# M-Controller_REV-A.net
KiCad netlist of a schematic drawn in EAGLE
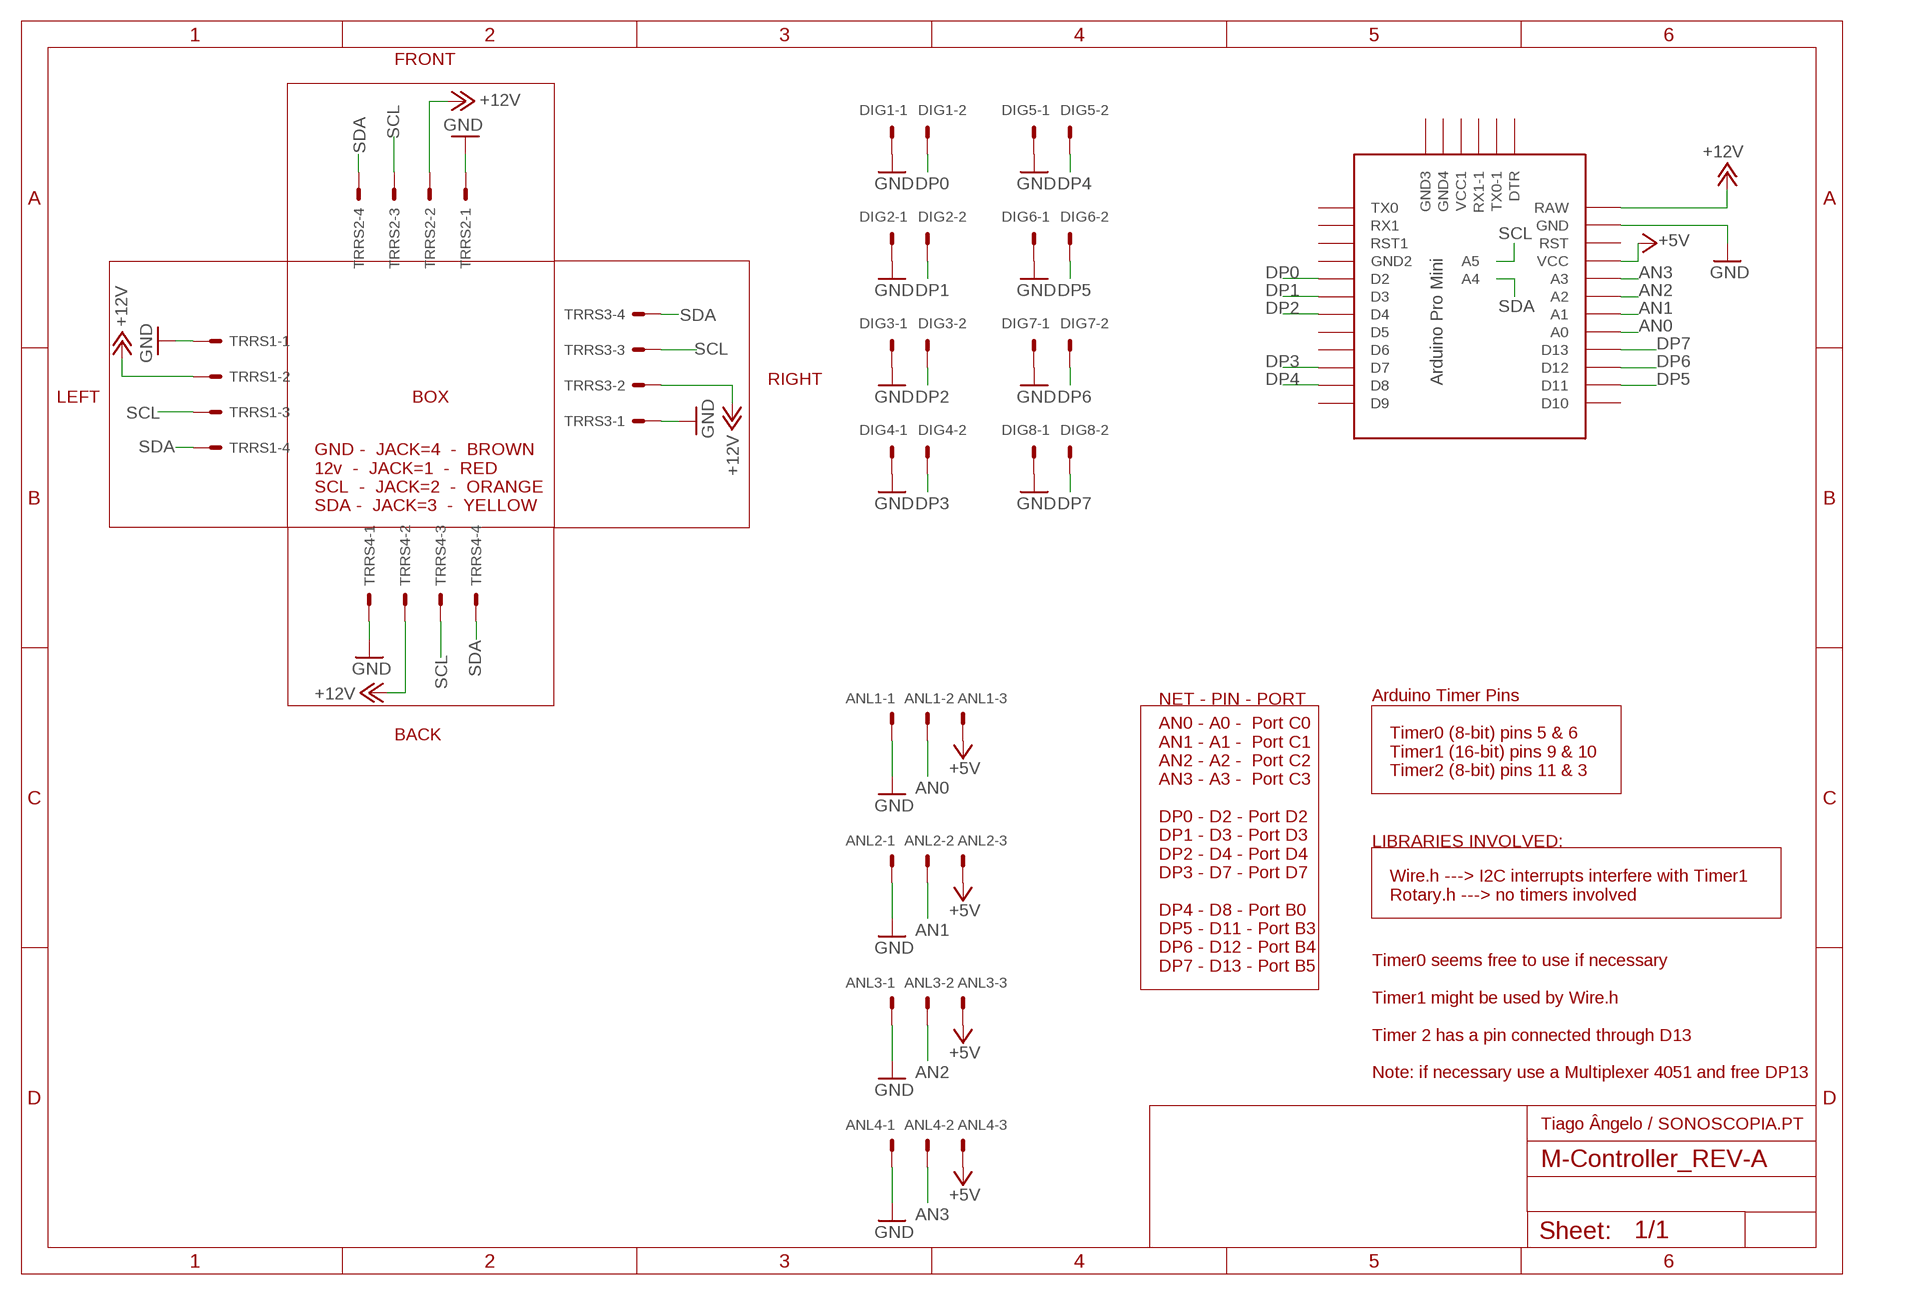
[diagram p0: schematic, sheet 1]

(export (version "E")
  (design (tool "Eeschema 10.0.6"))
  (components
    (comp (ref "ANL1")
      (value "22-27-2031-03")
      (footprint "eagle-import:6410-03")
      (libsource (lib "eagle-import") (part "22-?-0327-2031"))
    )
    (comp (ref "ANL2")
      (value "22-27-2031-03")
      (footprint "eagle-import:6410-03")
      (libsource (lib "eagle-import") (part "22-?-0327-2031"))
    )
    (comp (ref "ANL3")
      (value "22-27-2031-03")
      (footprint "eagle-import:6410-03")
      (libsource (lib "eagle-import") (part "22-?-0327-2031"))
    )
    (comp (ref "ANL4")
      (value "22-27-2031-03")
      (footprint "eagle-import:6410-03")
      (libsource (lib "eagle-import") (part "22-?-0327-2031"))
    )
    (comp (ref "DIG1")
      (value "22-27-2021-02")
      (footprint "eagle-import:6410-02")
      (libsource (lib "eagle-import") (part "22-?-0227-2021"))
    )
    (comp (ref "DIG2")
      (value "22-27-2021-02")
      (footprint "eagle-import:6410-02")
      (libsource (lib "eagle-import") (part "22-?-0227-2021"))
    )
    (comp (ref "DIG3")
      (value "22-27-2021-02")
      (footprint "eagle-import:6410-02")
      (libsource (lib "eagle-import") (part "22-?-0227-2021"))
    )
    (comp (ref "DIG4")
      (value "22-27-2021-02")
      (footprint "eagle-import:6410-02")
      (libsource (lib "eagle-import") (part "22-?-0227-2021"))
    )
    (comp (ref "DIG5")
      (value "22-27-2021-02")
      (footprint "eagle-import:6410-02")
      (libsource (lib "eagle-import") (part "22-?-0227-2021"))
    )
    (comp (ref "DIG6")
      (value "22-27-2021-02")
      (footprint "eagle-import:6410-02")
      (libsource (lib "eagle-import") (part "22-?-0227-2021"))
    )
    (comp (ref "DIG7")
      (value "22-27-2021-02")
      (footprint "eagle-import:6410-02")
      (libsource (lib "eagle-import") (part "22-?-0227-2021"))
    )
    (comp (ref "DIG8")
      (value "22-27-2021-02")
      (footprint "eagle-import:6410-02")
      (libsource (lib "eagle-import") (part "22-?-0227-2021"))
    )
    (comp (ref "TRRS1")
      (value "22-27-2041-04")
      (footprint "eagle-import:6410-04")
      (libsource (lib "eagle-import") (part "22-?-0427-2041"))
    )
    (comp (ref "TRRS2")
      (value "22-27-2041-04")
      (footprint "eagle-import:6410-04")
      (libsource (lib "eagle-import") (part "22-?-0427-2041"))
    )
    (comp (ref "TRRS3")
      (value "22-27-2041-04")
      (footprint "eagle-import:6410-04")
      (libsource (lib "eagle-import") (part "22-?-0427-2041"))
    )
    (comp (ref "TRRS4")
      (value "22-27-2041-04")
      (footprint "eagle-import:6410-04")
      (libsource (lib "eagle-import") (part "22-?-0427-2041"))
    )
    (comp (ref "U$1")
      (value "PRO-MINI-2")
      (footprint "eagle-import:PRO-MINI-2")
      (libsource (lib "eagle-import") (part "PRO-MINI-2"))
    )
  )
  (nets
    (net (code "1") (name "+5V") (class "Default")
      (node (ref "ANL1") (pin "3") (pinfunction "S_3") (pintype "passive"))
      (node (ref "ANL2") (pin "3") (pinfunction "S_3") (pintype "passive"))
      (node (ref "ANL3") (pin "3") (pinfunction "S_3") (pintype "passive"))
      (node (ref "ANL4") (pin "3") (pinfunction "S_3") (pintype "passive"))
      (node (ref "U$1") (pin "VCC") (pinfunction "VCC_VCC") (pintype "bidirectional"))
    )
    (net (code "2") (name "+12V") (class "Default")
      (node (ref "TRRS1") (pin "2") (pinfunction "S_2") (pintype "passive"))
      (node (ref "TRRS2") (pin "2") (pinfunction "S_2") (pintype "passive"))
      (node (ref "TRRS3") (pin "2") (pinfunction "S_2") (pintype "passive"))
      (node (ref "TRRS4") (pin "2") (pinfunction "S_2") (pintype "passive"))
      (node (ref "U$1") (pin "RAW") (pinfunction "RAW_RAW") (pintype "bidirectional"))
    )
    (net (code "3") (name "/AN0") (class "Default")
      (node (ref "ANL1") (pin "2") (pinfunction "S_2") (pintype "passive"))
      (node (ref "U$1") (pin "A0") (pinfunction "A0_A0") (pintype "bidirectional"))
    )
    (net (code "4") (name "/AN1") (class "Default")
      (node (ref "ANL2") (pin "2") (pinfunction "S_2") (pintype "passive"))
      (node (ref "U$1") (pin "A1") (pinfunction "A1_A1") (pintype "bidirectional"))
    )
    (net (code "5") (name "/AN2") (class "Default")
      (node (ref "ANL3") (pin "2") (pinfunction "S_2") (pintype "passive"))
      (node (ref "U$1") (pin "A2") (pinfunction "A2_A2") (pintype "bidirectional"))
    )
    (net (code "6") (name "/AN3") (class "Default")
      (node (ref "ANL4") (pin "2") (pinfunction "S_2") (pintype "passive"))
      (node (ref "U$1") (pin "A3") (pinfunction "A3_A3") (pintype "bidirectional"))
    )
    (net (code "7") (name "/DP0") (class "Default")
      (node (ref "DIG1") (pin "2") (pinfunction "S_2") (pintype "passive"))
      (node (ref "U$1") (pin "D2") (pinfunction "D2_D2") (pintype "bidirectional"))
    )
    (net (code "8") (name "/DP1") (class "Default")
      (node (ref "DIG2") (pin "2") (pinfunction "S_2") (pintype "passive"))
      (node (ref "U$1") (pin "D3") (pinfunction "D3_D3") (pintype "bidirectional"))
    )
    (net (code "9") (name "/DP2") (class "Default")
      (node (ref "DIG3") (pin "2") (pinfunction "S_2") (pintype "passive"))
      (node (ref "U$1") (pin "D4") (pinfunction "D4_D4") (pintype "bidirectional"))
    )
    (net (code "10") (name "/DP3") (class "Default")
      (node (ref "DIG4") (pin "2") (pinfunction "S_2") (pintype "passive"))
      (node (ref "U$1") (pin "D7") (pinfunction "D7_D7") (pintype "bidirectional"))
    )
    (net (code "11") (name "/DP4") (class "Default")
      (node (ref "DIG5") (pin "2") (pinfunction "S_2") (pintype "passive"))
      (node (ref "U$1") (pin "D8") (pinfunction "D8_D8") (pintype "bidirectional"))
    )
    (net (code "12") (name "/DP5") (class "Default")
      (node (ref "DIG6") (pin "2") (pinfunction "S_2") (pintype "passive"))
      (node (ref "U$1") (pin "D11") (pinfunction "D11_D11") (pintype "bidirectional"))
    )
    (net (code "13") (name "/DP6") (class "Default")
      (node (ref "DIG7") (pin "2") (pinfunction "S_2") (pintype "passive"))
      (node (ref "U$1") (pin "D12") (pinfunction "D12_D12") (pintype "bidirectional"))
    )
    (net (code "14") (name "/DP7") (class "Default")
      (node (ref "DIG8") (pin "2") (pinfunction "S_2") (pintype "passive"))
      (node (ref "U$1") (pin "D13") (pinfunction "D13_D13") (pintype "bidirectional"))
    )
    (net (code "15") (name "/SCL") (class "Default")
      (node (ref "TRRS1") (pin "3") (pinfunction "S_3") (pintype "passive"))
      (node (ref "TRRS2") (pin "3") (pinfunction "S_3") (pintype "passive"))
      (node (ref "TRRS3") (pin "3") (pinfunction "S_3") (pintype "passive"))
      (node (ref "TRRS4") (pin "3") (pinfunction "S_3") (pintype "passive"))
      (node (ref "U$1") (pin "A5") (pinfunction "A5_A5") (pintype "bidirectional"))
    )
    (net (code "16") (name "/SDA") (class "Default")
      (node (ref "TRRS1") (pin "4") (pinfunction "S_4") (pintype "passive"))
      (node (ref "TRRS2") (pin "4") (pinfunction "S_4") (pintype "passive"))
      (node (ref "TRRS3") (pin "4") (pinfunction "S_4") (pintype "passive"))
      (node (ref "TRRS4") (pin "4") (pinfunction "S_4") (pintype "passive"))
      (node (ref "U$1") (pin "A4") (pinfunction "A4_A4") (pintype "bidirectional"))
    )
    (net (code "17") (name "GND") (class "Default")
      (node (ref "ANL1") (pin "1") (pinfunction "S_1") (pintype "passive"))
      (node (ref "ANL2") (pin "1") (pinfunction "S_1") (pintype "passive"))
      (node (ref "ANL3") (pin "1") (pinfunction "S_1") (pintype "passive"))
      (node (ref "ANL4") (pin "1") (pinfunction "S_1") (pintype "passive"))
      (node (ref "DIG1") (pin "1") (pinfunction "S_1") (pintype "passive"))
      (node (ref "DIG2") (pin "1") (pinfunction "S_1") (pintype "passive"))
      (node (ref "DIG3") (pin "1") (pinfunction "S_1") (pintype "passive"))
      (node (ref "DIG4") (pin "1") (pinfunction "S_1") (pintype "passive"))
      (node (ref "DIG5") (pin "1") (pinfunction "S_1") (pintype "passive"))
      (node (ref "DIG6") (pin "1") (pinfunction "S_1") (pintype "passive"))
      (node (ref "DIG7") (pin "1") (pinfunction "S_1") (pintype "passive"))
      (node (ref "DIG8") (pin "1") (pinfunction "S_1") (pintype "passive"))
      (node (ref "TRRS1") (pin "1") (pinfunction "S_1") (pintype "passive"))
      (node (ref "TRRS2") (pin "1") (pinfunction "S_1") (pintype "passive"))
      (node (ref "TRRS3") (pin "1") (pinfunction "S_1") (pintype "passive"))
      (node (ref "TRRS4") (pin "1") (pinfunction "S_1") (pintype "passive"))
      (node (ref "U$1") (pin "GND") (pinfunction "GND_GND") (pintype "bidirectional"))
    )
    (net (code "18") (name "unconnected-(U$1-GND2-PadGND1)") (class "Default")
      (node (ref "U$1") (pin "GND1") (pinfunction "GND2_GND1") (pintype "bidirectional"))
    )
    (net (code "19") (name "unconnected-(U$1-GND3-PadGND2)") (class "Default")
      (node (ref "U$1") (pin "GND2") (pinfunction "GND3_GND2") (pintype "bidirectional"))
    )
    (net (code "20") (name "unconnected-(U$1-GND4-PadGND3)") (class "Default")
      (node (ref "U$1") (pin "GND3") (pinfunction "GND4_GND3") (pintype "bidirectional"))
    )
    (net (code "21") (name "unconnected-(U$1-PadD5)") (class "Default")
      (node (ref "U$1") (pin "D5") (pinfunction "D5_D5") (pintype "bidirectional"))
    )
    (net (code "22") (name "unconnected-(U$1-PadD6)") (class "Default")
      (node (ref "U$1") (pin "D6") (pinfunction "D6_D6") (pintype "bidirectional"))
    )
    (net (code "23") (name "unconnected-(U$1-PadD9)") (class "Default")
      (node (ref "U$1") (pin "D9") (pinfunction "D9_D9") (pintype "bidirectional"))
    )
    (net (code "24") (name "unconnected-(U$1-PadD10)") (class "Default")
      (node (ref "U$1") (pin "D10") (pinfunction "D10_D10") (pintype "bidirectional"))
    )
    (net (code "25") (name "unconnected-(U$1-PadDTR)") (class "Default")
      (node (ref "U$1") (pin "DTR") (pinfunction "DTR_DTR") (pintype "bidirectional"))
    )
    (net (code "26") (name "unconnected-(U$1-PadRST)") (class "Default")
      (node (ref "U$1") (pin "RST") (pinfunction "RST_RST") (pintype "bidirectional"))
    )
    (net (code "27") (name "unconnected-(U$1-PadRST1)") (class "Default")
      (node (ref "U$1") (pin "RST1") (pinfunction "RST1_RST1") (pintype "bidirectional"))
    )
    (net (code "28") (name "unconnected-(U$1-PadRX1)") (class "Default")
      (node (ref "U$1") (pin "RX1") (pinfunction "RX1_RX1") (pintype "bidirectional"))
    )
    (net (code "29") (name "unconnected-(U$1-PadRX1-1)") (class "Default")
      (node (ref "U$1") (pin "RX1-1") (pinfunction "RX1-1_RX1-1") (pintype "bidirectional"))
    )
    (net (code "30") (name "unconnected-(U$1-PadTX0)") (class "Default")
      (node (ref "U$1") (pin "TX0") (pinfunction "TX0_TX0") (pintype "bidirectional"))
    )
    (net (code "31") (name "unconnected-(U$1-PadTX0-1)") (class "Default")
      (node (ref "U$1") (pin "TX0-1") (pinfunction "TX0-1_TX0-1") (pintype "bidirectional"))
    )
    (net (code "32") (name "unconnected-(U$1-PadVCC1)") (class "Default")
      (node (ref "U$1") (pin "VCC1") (pinfunction "VCC1_VCC1") (pintype "bidirectional"))
    )
  )
)
